# BATTERY.net
KiCad netlist of a schematic drawn in Altium Designer
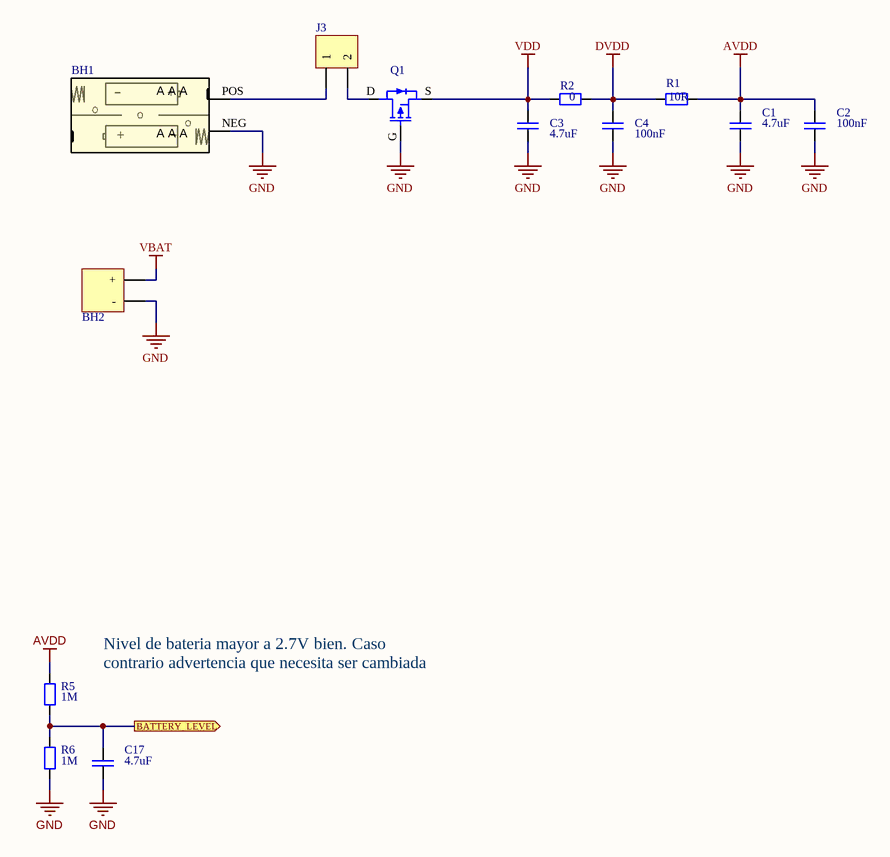
[diagram p0: BATTERY.SchDoc]

(export (version "E")
  (design (tool "Eeschema 10.0.6"))
  (components
    (comp (ref "BH1")
      (value "2468")
      (footprint "BATTERY_HOLDER_2XAAA")
      (description "2 x AAA through hole economic type")
      (fields
        (field (name "MANUFACTURER") "Keystone Electronics")
        (field (name "MANUFACTURER PART NUMBER") "2462")
      )
      (libsource (lib "Battery_Holders") (part "2468"))
    )
    (comp (ref "BH2")
      (value "Battery Holder CR2032")
      (footprint "BS-08-B2AA016")
      (description "Battery base -25℃~+85℃ CR2032 SMD Battery Connectors ROHS")
      (fields
        (field (name "MANUFACTURER") "Myoung")
        (field (name "MANUFACTURER PART NUMBER") "BS-08-B2AA016")
      )
      (libsource (lib "Battery_Holders") (part "BS-08-B2AA016"))
    )
    (comp (ref "C1")
      (value "4.7uF")
      (footprint "CAP_SM0805_YAGEOCC2_N")
      (description "CAP 4.7uF SM0805 X5R 10V YAGEO CC2")
      (fields
        (field (name "MANUFACTURER") "Yageo")
        (field (name "MANUFACTURER PART NUMBER") "CC0805KRX5R6BB475")
      )
      (libsource (lib "Yageo") (part "CC0805KRX5R6BB475"))
    )
    (comp (ref "C2")
      (value "100nF")
      (footprint "CAP_SM0805_YAGEOCC2_N")
      (description "CAP 100nF SM0805 X7R 25V YAGEO CC2")
      (fields
        (field (name "MANUFACTURER") "Yageo")
        (field (name "MANUFACTURER PART NUMBER") "CC0805KRX7R8BB104")
      )
      (libsource (lib "Yageo") (part "CC0805KRX7R8BB104"))
    )
    (comp (ref "C3")
      (value "4.7uF")
      (footprint "CAP_SM0805_YAGEOCC2_N")
      (description "CAP 4.7uF SM0805 X5R 10V YAGEO CC2")
      (fields
        (field (name "MANUFACTURER") "Yageo")
        (field (name "MANUFACTURER PART NUMBER") "CC0805KRX5R6BB475")
      )
      (libsource (lib "Yageo") (part "CC0805KRX5R6BB475"))
    )
    (comp (ref "C4")
      (value "100nF")
      (footprint "CAP_SM0805_YAGEOCC2_N")
      (description "CAP 100nF SM0805 X7R 25V YAGEO CC2")
      (fields
        (field (name "MANUFACTURER") "Yageo")
        (field (name "MANUFACTURER PART NUMBER") "CC0805KRX7R8BB104")
      )
      (libsource (lib "Yageo") (part "CC0805KRX7R8BB104"))
    )
    (comp (ref "C17")
      (value "4.7uF")
      (footprint "CAP_SM0805_YAGEOCC2_N")
      (description "CAP 4.7uF SM0805 X5R 10V YAGEO CC2")
      (fields
        (field (name "MANUFACTURER") "Yageo")
        (field (name "MANUFACTURER PART NUMBER") "CC0805KRX5R6BB475")
      )
      (libsource (lib "Yageo") (part "CC0805KRX5R6BB475"))
    )
    (comp (ref "J3")
      (value "Usar Equivalente")
      (footprint "HEADER PIN 1X2")
      (description "1 x 2 - true hole  2.54mm - Pb free")
      (fields
        (field (name "MANUFACTURER") "Amphenol ICC")
        (field (name "MANUFACTURER PART NUMBER") "54101-T0602LF")
      )
      (libsource (lib "header_pin") (part "54101-T0602LF"))
    )
    (comp (ref "Q1")
      (value "DMG3401LSN-7")
      (footprint "DMG3401LSN-7")
      (description "P-CHANNEL ENHANCEMENT MODE MOSFET\r\nRDS(ON) = 85mΩ @ VGS = -2.5V -> ID -2.7A\r\nV(BR)DDS 30V")
      (fields (field (name "MANUFACTURER") "Diodes Incorporated"))
      (libsource (lib "mosfet") (part "DMG3401LSN-7"))
    )
    (comp (ref "R1")
      (value "10R")
      (footprint "RES_SM0805_YAGEORC_N")
      (description "RES 10R SM0805 YAGEO RC_L")
      (fields
        (field (name "MANUFACTURER") "Yageo")
        (field (name "MANUFACTURER PART NUMBER") "RC0805FR-0710RL")
      )
      (libsource (lib "Yageo") (part "RC0805FR-0710RL"))
    )
    (comp (ref "R2")
      (value "0")
      (footprint "RES_SM0805_YAGEORC_N")
      (description "RES 0 OHMS SM0805 YAGEO RC_L")
      (fields
        (field (name "MANUFACTURER") "Yageo")
        (field (name "MANUFACTURER PART NUMBER") "RC0603FR-070RL")
      )
      (libsource (lib "Yageo") (part "RC0805JR-070RL"))
    )
    (comp (ref "R5")
      (value "1M")
      (footprint "RES_SM0805_YAGEORC_N")
      (description "RES 1M SM0805 YAGEO RC_L")
      (fields
        (field (name "MANUFACTURER") "Yageo")
        (field (name "MANUFACTURER PART NUMBER") "RC0805FR-071ML")
      )
      (libsource (lib "Yageo") (part "RC0805FR-071ML"))
    )
    (comp (ref "R6")
      (value "1M")
      (footprint "RES_SM0805_YAGEORC_N")
      (description "RES 1M SM0805 YAGEO RC_L")
      (fields
        (field (name "MANUFACTURER") "Yageo")
        (field (name "MANUFACTURER PART NUMBER") "RC0805FR-071ML")
      )
      (libsource (lib "Yageo") (part "RC0805FR-071ML"))
    )
  )
  (nets
    (net (code "1") (name "/BATTERY_LEVEL") (class "Default")
      (node (ref "C17") (pin "1") (pintype "passive"))
      (node (ref "R5") (pin "1") (pintype "passive"))
      (node (ref "R6") (pin "2") (pintype "passive"))
    )
    (net (code "2") (name "AVDD") (class "Default")
      (node (ref "C1") (pin "1") (pintype "passive"))
      (node (ref "C2") (pin "1") (pintype "passive"))
      (node (ref "R1") (pin "2") (pintype "passive"))
      (node (ref "R5") (pin "2") (pintype "passive"))
    )
    (net (code "3") (name "DVDD") (class "Default")
      (node (ref "C4") (pin "1") (pintype "passive"))
      (node (ref "R1") (pin "1") (pintype "passive"))
      (node (ref "R2") (pin "2") (pintype "passive"))
    )
    (net (code "4") (name "GND") (class "Default")
      (node (ref "BH1") (pin "NEG") (pinfunction "NEG_NEG") (pintype "passive"))
      (node (ref "BH2") (pin "NEG") (pinfunction "-_NEG") (pintype "passive"))
      (node (ref "C1") (pin "2") (pintype "passive"))
      (node (ref "C17") (pin "2") (pintype "passive"))
      (node (ref "C2") (pin "2") (pintype "passive"))
      (node (ref "C3") (pin "2") (pintype "passive"))
      (node (ref "C4") (pin "2") (pintype "passive"))
      (node (ref "Q1") (pin "G") (pinfunction "G_G") (pintype "passive"))
      (node (ref "R6") (pin "1") (pintype "passive"))
    )
    (net (code "5") (name "Net-(BH1-PadPOS)") (class "Default")
      (node (ref "BH1") (pin "POS") (pinfunction "POS_POS") (pintype "passive"))
      (node (ref "J3") (pin "1") (pinfunction "1_1") (pintype "passive"))
    )
    (net (code "6") (name "Net-(J3-Pad2)") (class "Default")
      (node (ref "J3") (pin "2") (pinfunction "2_2") (pintype "passive"))
      (node (ref "Q1") (pin "D") (pinfunction "D_D") (pintype "passive"))
    )
    (net (code "7") (name "VBAT") (class "Default")
      (node (ref "BH2") (pin "POS") (pinfunction "+_POS") (pintype "passive"))
    )
    (net (code "8") (name "VDD") (class "Default")
      (node (ref "C3") (pin "1") (pintype "passive"))
      (node (ref "Q1") (pin "S") (pinfunction "S_S") (pintype "passive"))
      (node (ref "R2") (pin "1") (pintype "passive"))
    )
  )
)
